# ProPrj_NavBot-ChargeModule-2S_2026-01-14.net
KiCad netlist of a schematic drawn in EasyEDA Pro
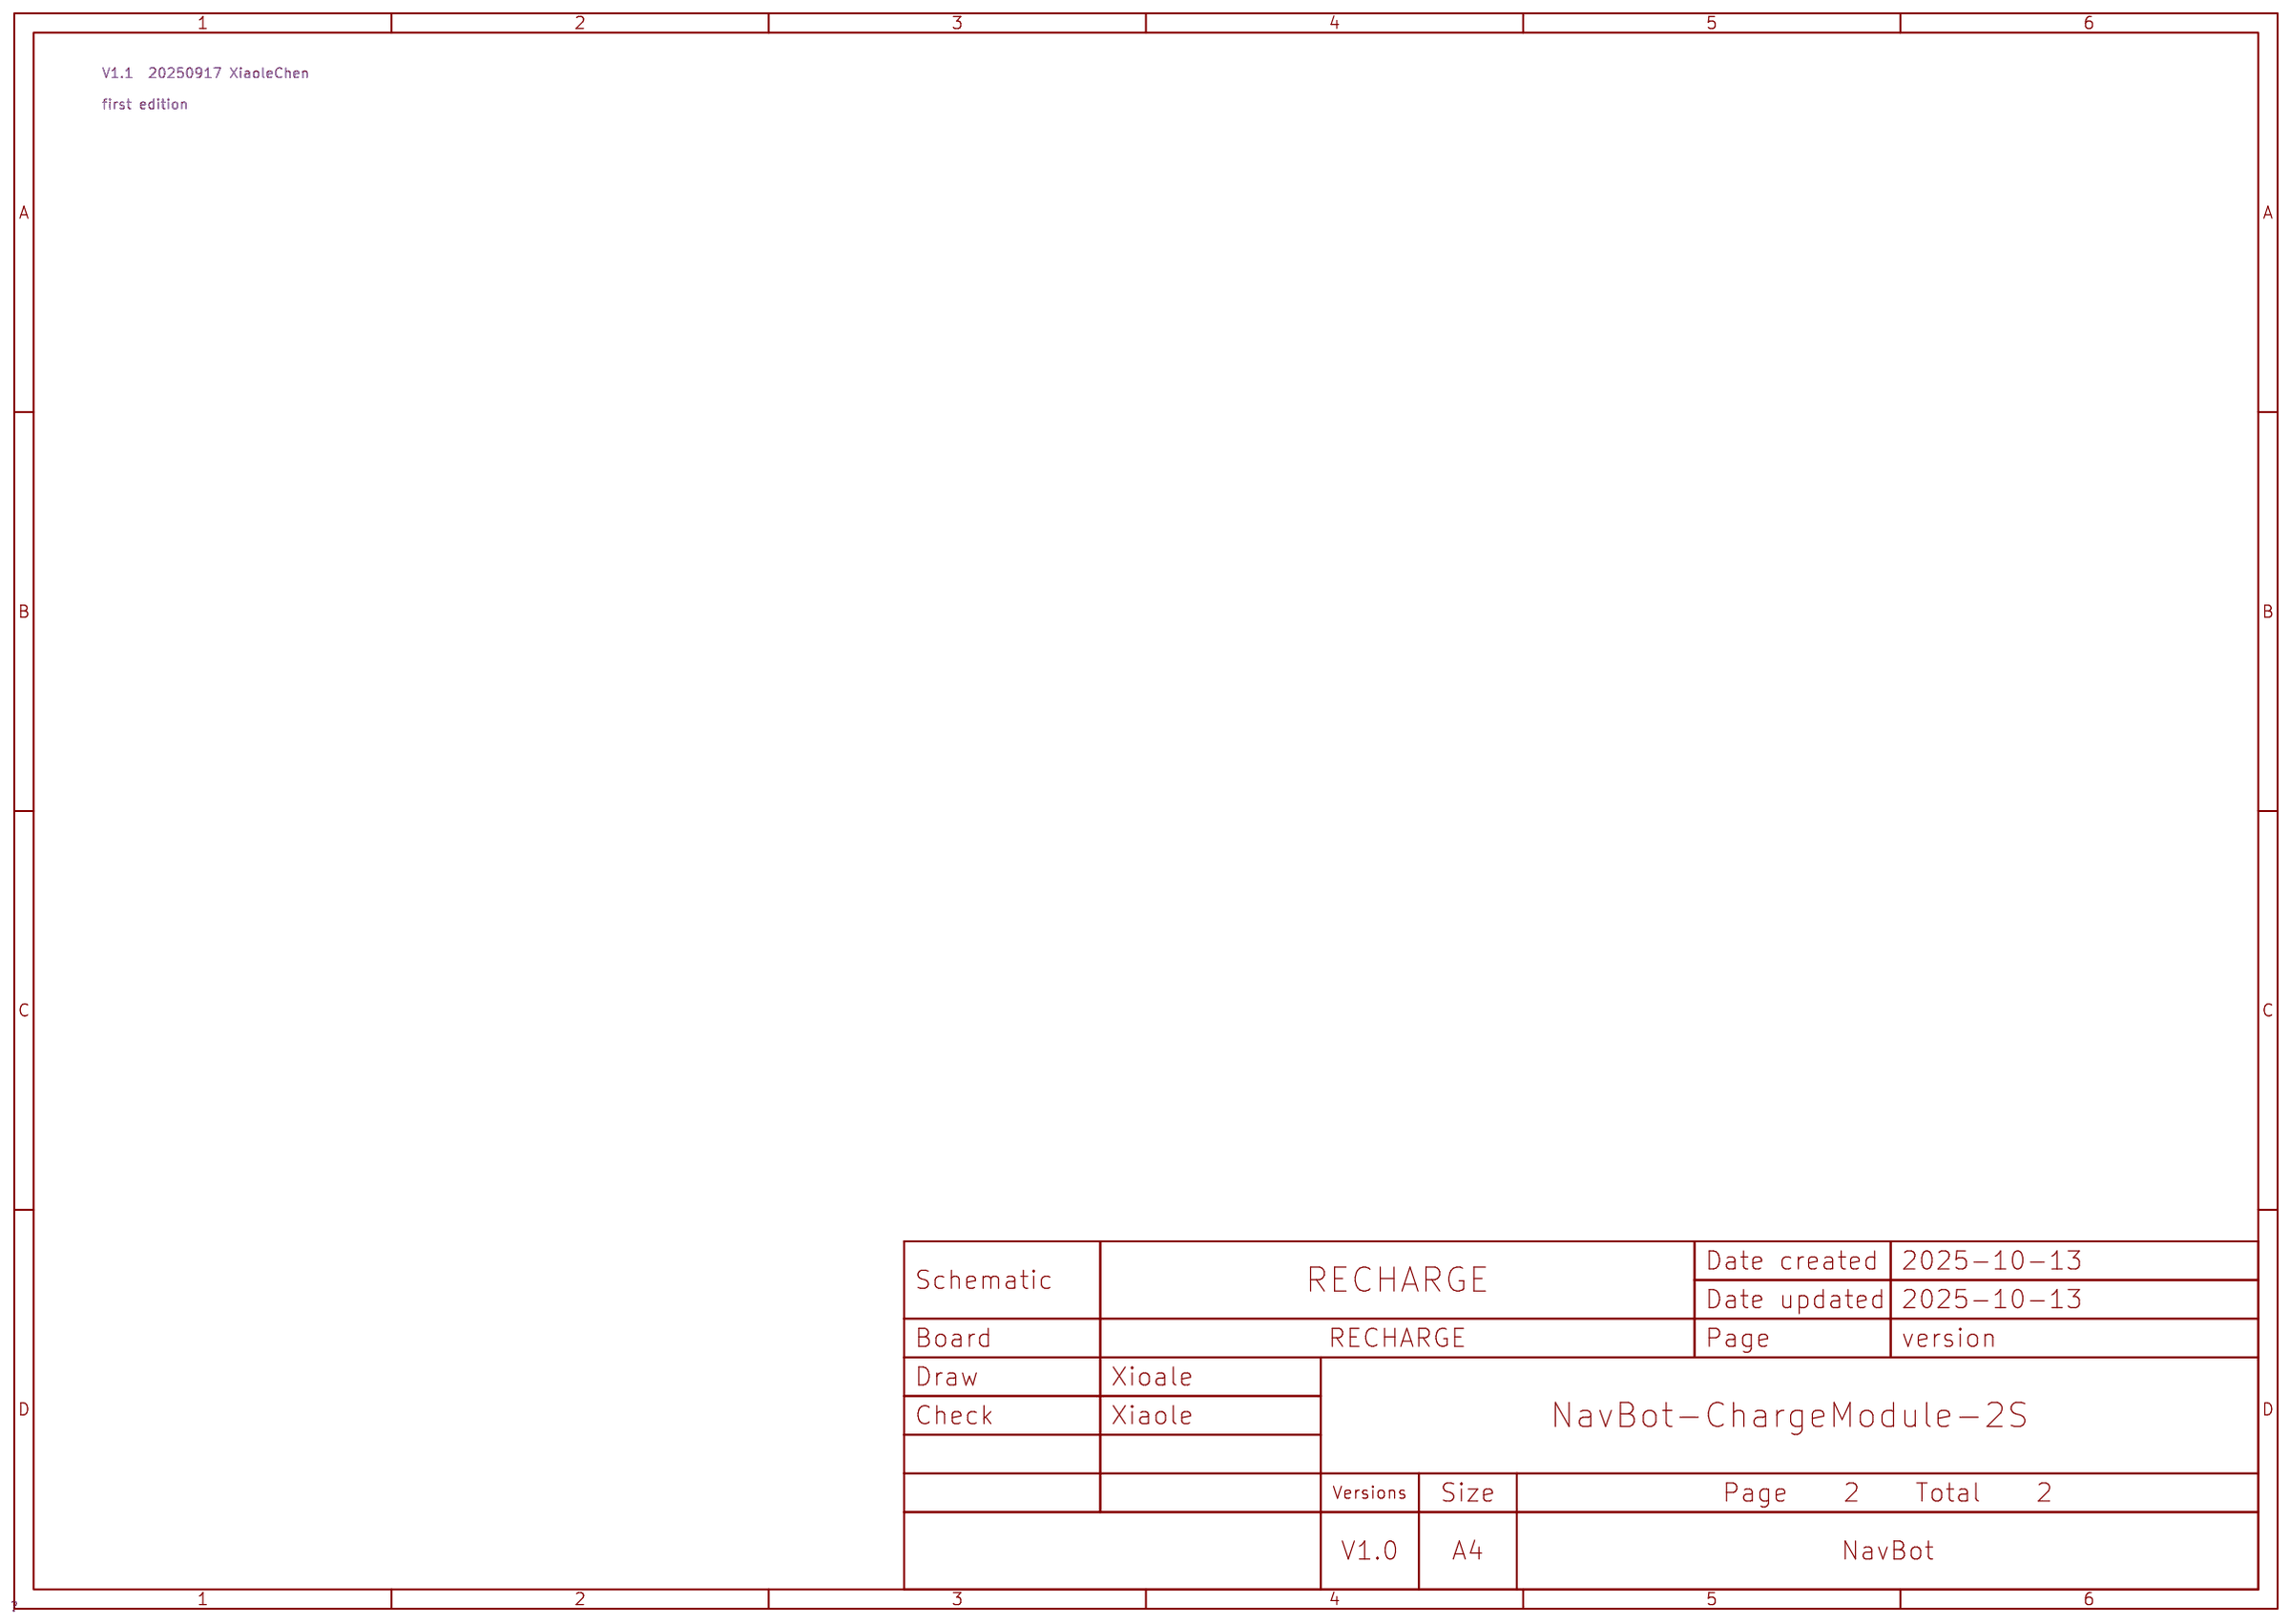
[diagram p0: version]
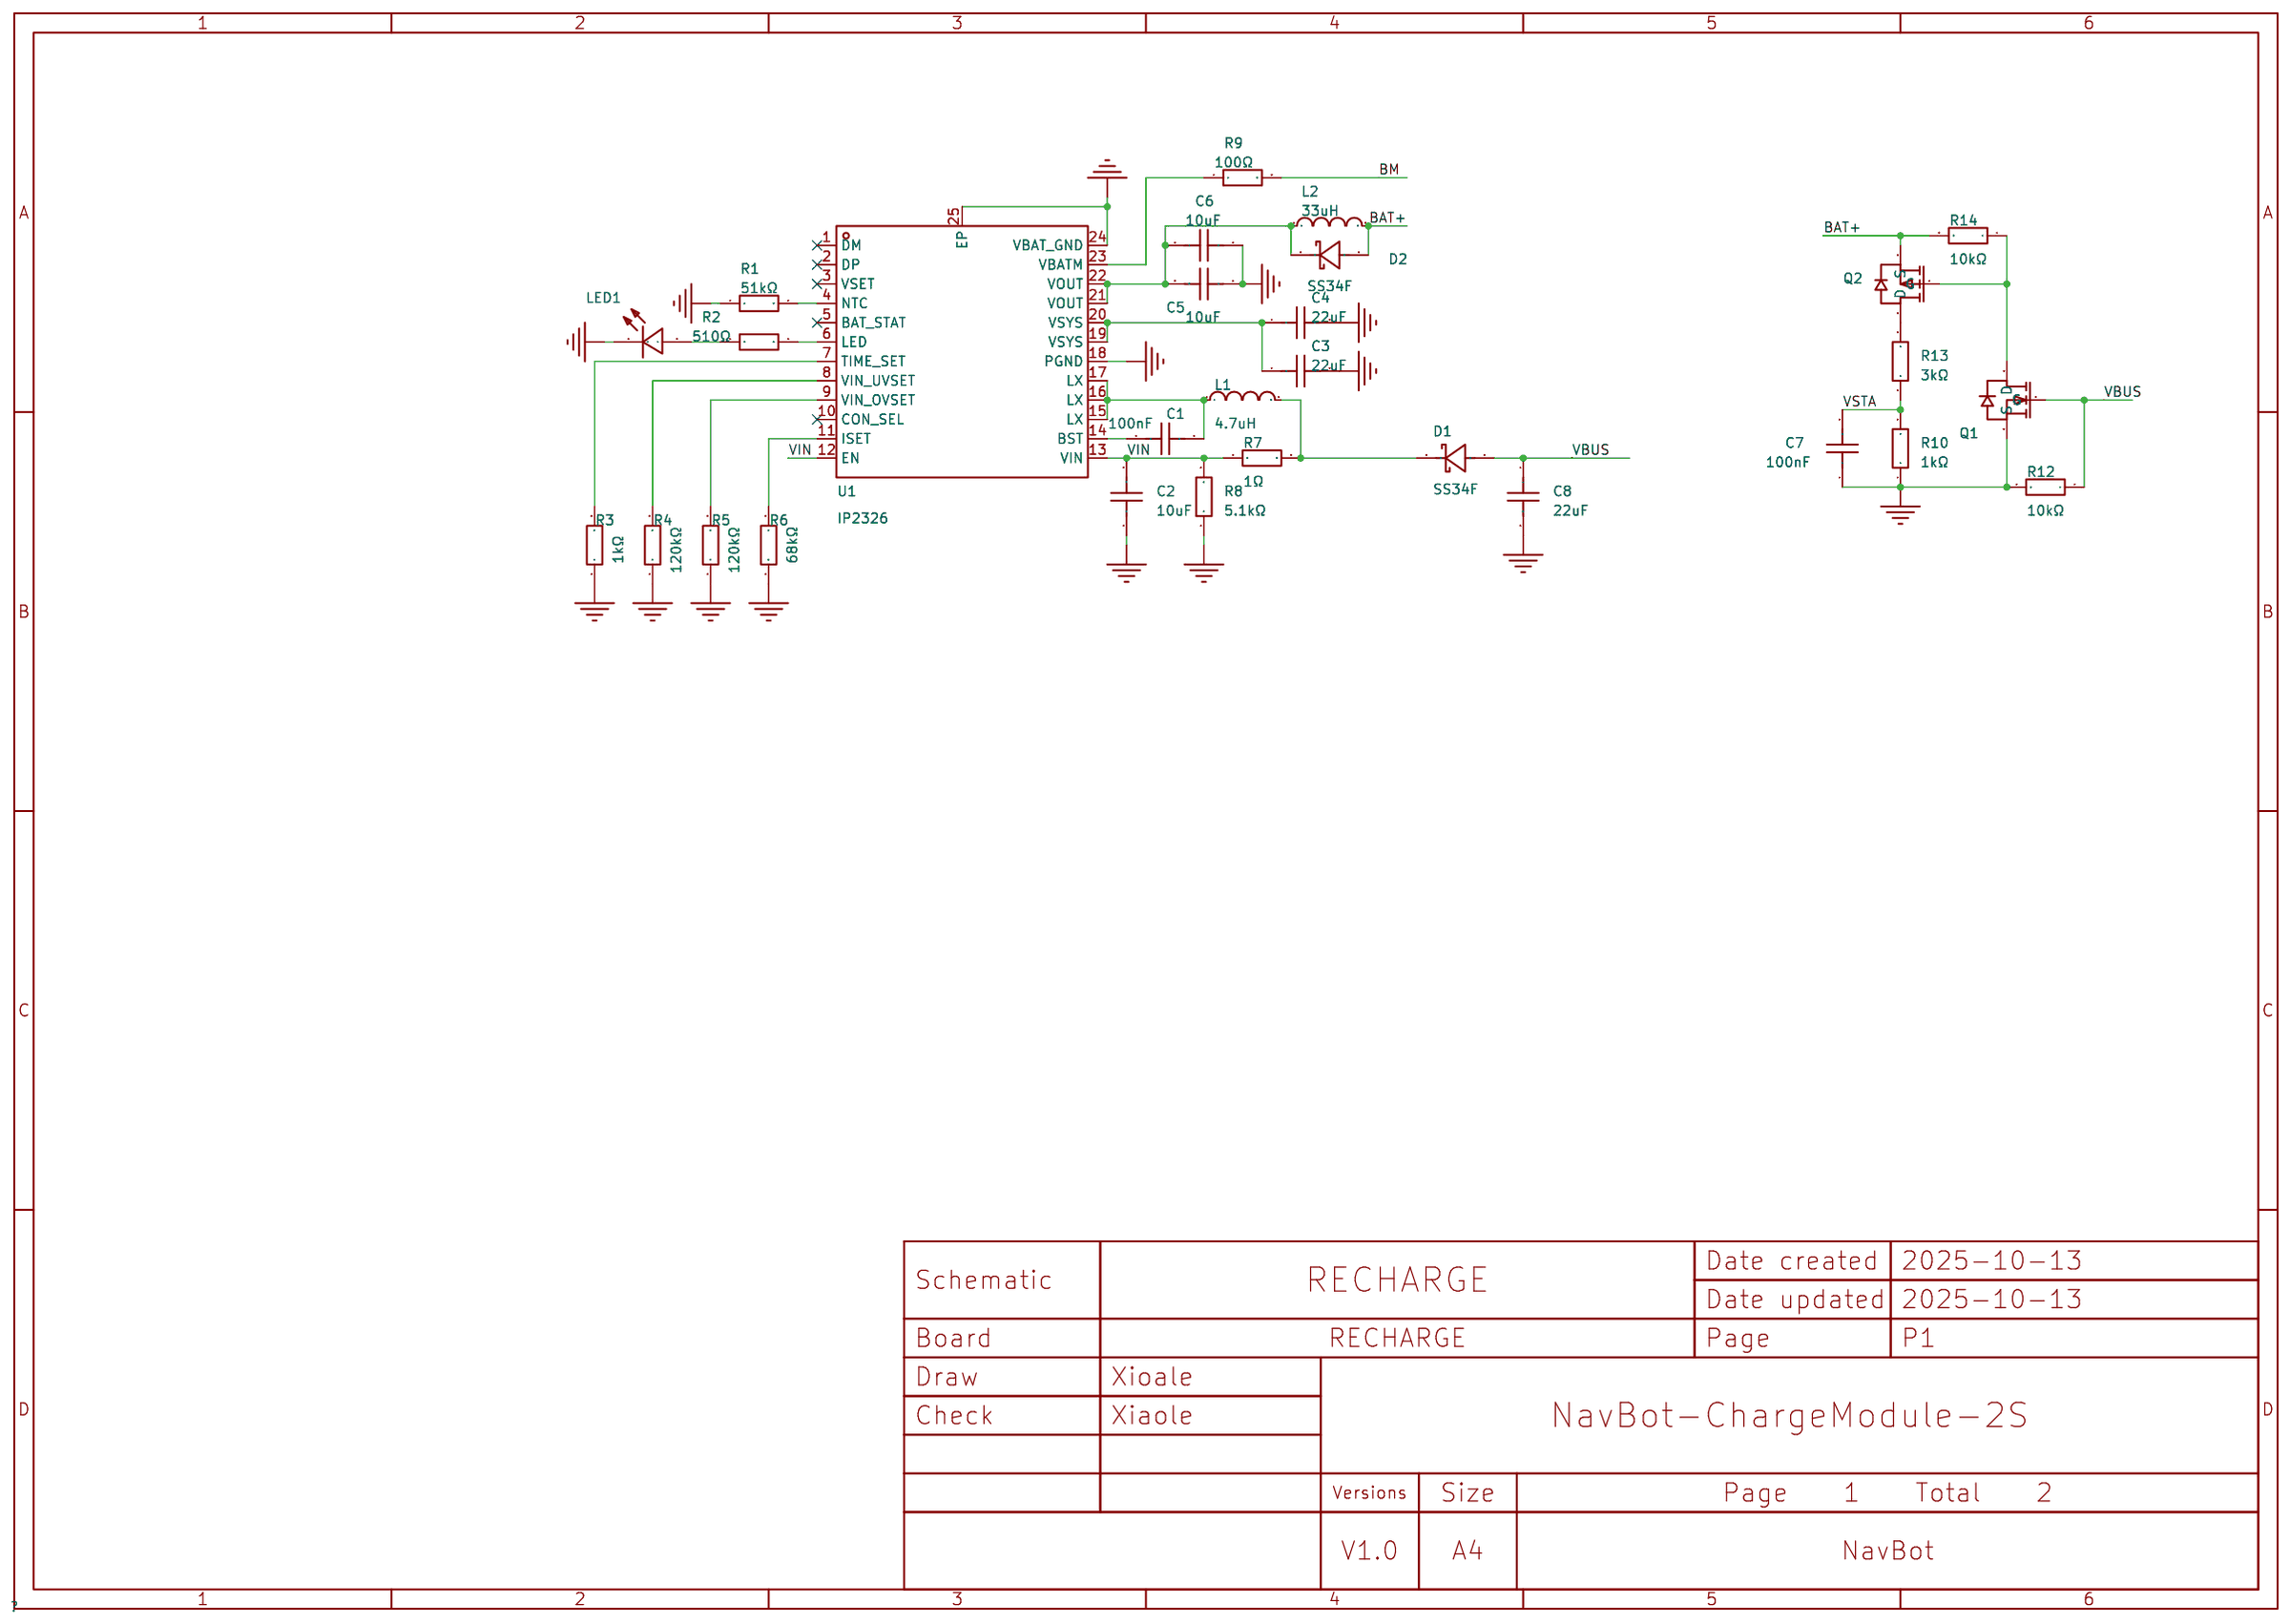
[diagram p1: P1]

(export (version "E")
  (design (tool "Eeschema 10.0.6"))
  (components
    (comp (ref "C1")
      (value "100nF")
      (footprint "easyedapro:C0603")
      (fields
        (field (name "Manufacturer Part") "CC0603KRX7R9BB104")
        (field (name "Manufacturer") "YAGEO(国巨)")
      )
      (libsource (lib "easyedapro") (part "CC0603KRX7R9BB104"))
    )
    (comp (ref "C2")
      (value "10uF")
      (footprint "easyedapro:C0603")
      (fields
        (field (name "Manufacturer Part") "CL10A106MA8NRNC")
        (field (name "Manufacturer") "SAMSUNG(三星)")
      )
      (libsource (lib "easyedapro") (part "CL10A106MA8NRNC"))
    )
    (comp (ref "C3")
      (value "22uF")
      (footprint "easyedapro:C0805")
      (fields
        (field (name "Manufacturer Part") "CL21A226MAQNNNE")
        (field (name "Manufacturer") "SAMSUNG(三星)")
      )
      (libsource (lib "easyedapro") (part "CL21A226MAQNNNE"))
    )
    (comp (ref "C4")
      (value "22uF")
      (footprint "easyedapro:C0805")
      (fields
        (field (name "Manufacturer Part") "CL21A226MAQNNNE")
        (field (name "Manufacturer") "SAMSUNG(三星)")
      )
      (libsource (lib "easyedapro") (part "CL21A226MAQNNNE"))
    )
    (comp (ref "C5")
      (value "10uF")
      (footprint "easyedapro:C0603")
      (fields
        (field (name "Manufacturer Part") "CL10A106MA8NRNC")
        (field (name "Manufacturer") "SAMSUNG(三星)")
      )
      (libsource (lib "easyedapro") (part "CL10A106MA8NRNC"))
    )
    (comp (ref "C6")
      (value "10uF")
      (footprint "easyedapro:C0603")
      (fields
        (field (name "Manufacturer Part") "CL10A106MA8NRNC")
        (field (name "Manufacturer") "SAMSUNG(三星)")
      )
      (libsource (lib "easyedapro") (part "CL10A106MA8NRNC"))
    )
    (comp (ref "C7")
      (value "100nF")
      (footprint "easyedapro:C0603")
      (fields
        (field (name "Manufacturer Part") "CC0603KRX7R9BB104")
        (field (name "Manufacturer") "YAGEO(国巨)")
      )
      (libsource (lib "easyedapro") (part "CC0603KRX7R9BB104"))
    )
    (comp (ref "C8")
      (value "22uF")
      (footprint "easyedapro:C0805")
      (fields
        (field (name "Manufacturer Part") "CL21A226MAQNNNE")
        (field (name "Manufacturer") "SAMSUNG(三星)")
      )
      (libsource (lib "easyedapro") (part "CL21A226MAQNNNE"))
    )
    (comp (ref "D1")
      (value "SS34F")
      (footprint "easyedapro:SMAF_L3.5-W2.6-LS4.7-RD-1")
      (fields (field (name "Manufacturer") "R+O(宏嘉诚)"))
      (libsource (lib "easyedapro") (part "SS34F_C18199199"))
    )
    (comp (ref "D2")
      (value "SS34F")
      (footprint "easyedapro:SMAF_L3.5-W2.6-LS4.7-RD-1")
      (fields (field (name "Manufacturer") "R+O(宏嘉诚)"))
      (libsource (lib "easyedapro") (part "SS34F_C18199199"))
    )
    (comp (ref "L1")
      (value "4.7uH")
      (footprint "easyedapro:IND-SMD_L4.0-W4.0")
      (fields
        (field (name "Manufacturer Part") "FHD4012S-4R7MT")
        (field (name "Manufacturer") "cjiang(长江微电)")
      )
      (libsource (lib "easyedapro") (part "FHD4012S-4R7MT"))
    )
    (comp (ref "L2")
      (value "33uH")
      (footprint "easyedapro:IND-SMD_L4.0-W4.0")
      (fields
        (field (name "Manufacturer Part") "FHD4020S-330MT")
        (field (name "Manufacturer") "cjiang(长江微电)")
      )
      (libsource (lib "easyedapro") (part "FHD4020S-330MT"))
    )
    (comp (ref "LED1")
      (value "KT-0603R")
      (footprint "easyedapro:LED0603-RD")
      (fields (field (name "Manufacturer") "KENTO"))
      (libsource (lib "easyedapro") (part "KT-0603R"))
    )
    (comp (ref "Q1")
      (value "~")
      (footprint "easyedapro:SOT-23-3_L2.9-W1.3-P1.90-LS2.4-BR")
      (libsource (lib "easyedapro") (part "N_MOS"))
    )
    (comp (ref "Q2")
      (value "~")
      (footprint "easyedapro:AO3401A_SOT-23-3")
      (libsource (lib "easyedapro") (part "P_MOS"))
    )
    (comp (ref "R1")
      (value "51kΩ")
      (footprint "easyedapro:R0603")
      (fields
        (field (name "Manufacturer Part") "0603WAF5102T5E")
        (field (name "Manufacturer") "UNI-ROYAL(厚声)")
      )
      (libsource (lib "easyedapro") (part "0603WAF5102T5E"))
    )
    (comp (ref "R2")
      (value "510Ω")
      (footprint "easyedapro:R0603")
      (fields
        (field (name "Manufacturer Part") "0603WAF5100T5E")
        (field (name "Manufacturer") "UNI-ROYAL(厚声)")
      )
      (libsource (lib "easyedapro") (part "0603WAF5100T5E"))
    )
    (comp (ref "R3")
      (value "1kΩ")
      (footprint "easyedapro:R0603")
      (fields
        (field (name "Manufacturer Part") "0603WAF1001T5E")
        (field (name "Manufacturer") "UNI-ROYAL(厚声)")
      )
      (libsource (lib "easyedapro") (part "0603WAF1001T5E"))
    )
    (comp (ref "R4")
      (value "120kΩ")
      (footprint "easyedapro:R0603")
      (fields
        (field (name "Manufacturer Part") "0603WAF1203T5E")
        (field (name "Manufacturer") "UNI-ROYAL(厚声)")
      )
      (libsource (lib "easyedapro") (part "0603WAF1203T5E"))
    )
    (comp (ref "R5")
      (value "120kΩ")
      (footprint "easyedapro:R0603")
      (fields
        (field (name "Manufacturer Part") "0603WAF1203T5E")
        (field (name "Manufacturer") "UNI-ROYAL(厚声)")
      )
      (libsource (lib "easyedapro") (part "0603WAF1203T5E"))
    )
    (comp (ref "R6")
      (value "68kΩ")
      (footprint "easyedapro:R0603")
      (fields
        (field (name "Manufacturer Part") "0603WAF6802T5E")
        (field (name "Manufacturer") "UNI-ROYAL(厚声)")
      )
      (libsource (lib "easyedapro") (part "0603WAF6802T5E"))
    )
    (comp (ref "R7")
      (value "1Ω")
      (footprint "easyedapro:R0603")
      (fields
        (field (name "Manufacturer Part") "0603WAF100KT5E")
        (field (name "Manufacturer") "UNI-ROYAL(厚声)")
      )
      (libsource (lib "easyedapro") (part "0603WAF100KT5E"))
    )
    (comp (ref "R8")
      (value "5.1kΩ")
      (footprint "easyedapro:R0603")
      (fields
        (field (name "Manufacturer Part") "0603WAF5101T5E")
        (field (name "Manufacturer") "UNI-ROYAL(厚声)")
      )
      (libsource (lib "easyedapro") (part "0603WAF5101T5E"))
    )
    (comp (ref "R9")
      (value "100Ω")
      (footprint "easyedapro:R1206")
      (fields
        (field (name "Manufacturer Part") "1206W4F1000T5E")
        (field (name "Manufacturer") "UNI-ROYAL(厚声)")
      )
      (libsource (lib "easyedapro") (part "1206W4F1000T5E"))
    )
    (comp (ref "R10")
      (value "1kΩ")
      (footprint "easyedapro:R0603")
      (fields
        (field (name "Manufacturer Part") "0603WAF1001T5E")
        (field (name "Manufacturer") "UNI-ROYAL(厚声)")
      )
      (libsource (lib "easyedapro") (part "0603WAF1001T5E"))
    )
    (comp (ref "R12")
      (value "10kΩ")
      (footprint "easyedapro:R0603")
      (fields
        (field (name "Manufacturer Part") "0603WAF1002T5E")
        (field (name "Manufacturer") "UNI-ROYAL(厚声)")
      )
      (libsource (lib "easyedapro") (part "0603WAF1002T5E"))
    )
    (comp (ref "R13")
      (value "3kΩ")
      (footprint "easyedapro:R0603")
      (fields
        (field (name "Manufacturer Part") "0603WAF3001T5E")
        (field (name "Manufacturer") "UNI-ROYAL(厚声)")
      )
      (libsource (lib "easyedapro") (part "0603WAF3001T5E"))
    )
    (comp (ref "R14")
      (value "10kΩ")
      (footprint "easyedapro:R0603")
      (fields
        (field (name "Manufacturer Part") "0603WAF1002T5E")
        (field (name "Manufacturer") "UNI-ROYAL(厚声)")
      )
      (libsource (lib "easyedapro") (part "0603WAF1002T5E"))
    )
    (comp (ref "U1")
      (value "IP2326")
      (footprint "easyedapro:VQFN-24_L4.0-W4.0-P0.50-BL-EP2.5")
      (fields (field (name "Manufacturer") "INJOINIC(英集芯)"))
      (libsource (lib "easyedapro") (part "IP2326"))
    )
  )
  (nets
    (net (code "1") (name "BAT+") (class "Default")
      (node (ref "D2") (pin "2") (pinfunction "A_2") (pintype "unspecified"))
      (node (ref "L2") (pin "2") (pinfunction "2_2") (pintype "unspecified"))
      (node (ref "Q2") (pin "2") (pinfunction "S_2") (pintype "input"))
      (node (ref "R14") (pin "2") (pinfunction "2_2") (pintype "input"))
    )
    (net (code "2") (name "BM") (class "Default")
      (node (ref "R9") (pin "2") (pinfunction "2_2") (pintype "input"))
    )
    (net (code "3") (name "GND") (class "Default")
      (node (ref "C2") (pin "1") (pinfunction "1_1") (pintype "unspecified"))
      (node (ref "C3") (pin "2") (pinfunction "2_2") (pintype "unspecified"))
      (node (ref "C4") (pin "2") (pinfunction "2_2") (pintype "unspecified"))
      (node (ref "C5") (pin "1") (pinfunction "1_1") (pintype "unspecified"))
      (node (ref "C6") (pin "1") (pinfunction "1_1") (pintype "unspecified"))
      (node (ref "C7") (pin "1") (pinfunction "1_1") (pintype "unspecified"))
      (node (ref "C8") (pin "2") (pinfunction "2_2") (pintype "unspecified"))
      (node (ref "LED1") (pin "1") (pinfunction "K_1") (pintype "unspecified"))
      (node (ref "Q1") (pin "2") (pinfunction "S_2") (pintype "input"))
      (node (ref "R1") (pin "1") (pinfunction "1_1") (pintype "input"))
      (node (ref "R10") (pin "1") (pinfunction "1_1") (pintype "input"))
      (node (ref "R12") (pin "2") (pinfunction "2_2") (pintype "input"))
      (node (ref "R3") (pin "1") (pinfunction "1_1") (pintype "input"))
      (node (ref "R4") (pin "1") (pinfunction "1_1") (pintype "input"))
      (node (ref "R5") (pin "1") (pinfunction "1_1") (pintype "input"))
      (node (ref "R6") (pin "1") (pinfunction "1_1") (pintype "input"))
      (node (ref "R8") (pin "1") (pinfunction "1_1") (pintype "input"))
      (node (ref "U1") (pin "18") (pinfunction "PGND_18") (pintype "unspecified"))
      (node (ref "U1") (pin "24") (pinfunction "VBAT_GND_24") (pintype "unspecified"))
      (node (ref "U1") (pin "25") (pinfunction "EP_25") (pintype "unspecified"))
    )
    (net (code "4") (name "Net-(C1-Pad2)") (class "Default")
      (node (ref "C1") (pin "2") (pinfunction "2_2") (pintype "unspecified"))
      (node (ref "L1") (pin "1") (pinfunction "1_1") (pintype "unspecified"))
      (node (ref "U1") (pin "15") (pinfunction "LX_15") (pintype "unspecified"))
      (node (ref "U1") (pin "16") (pinfunction "LX_16") (pintype "unspecified"))
      (node (ref "U1") (pin "17") (pinfunction "LX_17") (pintype "unspecified"))
    )
    (net (code "5") (name "Net-(C3-Pad1)") (class "Default")
      (node (ref "C3") (pin "1") (pinfunction "1_1") (pintype "unspecified"))
      (node (ref "C4") (pin "1") (pinfunction "1_1") (pintype "unspecified"))
      (node (ref "U1") (pin "19") (pinfunction "VSYS_19") (pintype "unspecified"))
      (node (ref "U1") (pin "20") (pinfunction "VSYS_20") (pintype "unspecified"))
    )
    (net (code "6") (name "Net-(D1-K)") (class "Default")
      (node (ref "D1") (pin "1") (pinfunction "K_1") (pintype "unspecified"))
      (node (ref "L1") (pin "2") (pinfunction "2_2") (pintype "unspecified"))
      (node (ref "R7") (pin "2") (pinfunction "2_2") (pintype "input"))
    )
    (net (code "7") (name "Net-(D2-K)") (class "Default")
      (node (ref "C5") (pin "2") (pinfunction "2_2") (pintype "unspecified"))
      (node (ref "C6") (pin "2") (pinfunction "2_2") (pintype "unspecified"))
      (node (ref "D2") (pin "1") (pinfunction "K_1") (pintype "unspecified"))
      (node (ref "L2") (pin "1") (pinfunction "1_1") (pintype "unspecified"))
      (node (ref "U1") (pin "21") (pinfunction "VOUT_21") (pintype "unspecified"))
      (node (ref "U1") (pin "22") (pinfunction "VOUT_22") (pintype "unspecified"))
    )
    (net (code "8") (name "Net-(LED1-A)") (class "Default")
      (node (ref "LED1") (pin "2") (pinfunction "A_2") (pintype "unspecified"))
      (node (ref "R2") (pin "1") (pinfunction "1_1") (pintype "input"))
    )
    (net (code "9") (name "Net-(Q1-D)") (class "Default")
      (node (ref "Q1") (pin "3") (pinfunction "D_3") (pintype "input"))
      (node (ref "Q2") (pin "1") (pinfunction "G_1") (pintype "input"))
      (node (ref "R14") (pin "1") (pinfunction "1_1") (pintype "input"))
    )
    (net (code "10") (name "Net-(Q2-D)") (class "Default")
      (node (ref "Q2") (pin "3") (pinfunction "D_3") (pintype "input"))
      (node (ref "R13") (pin "2") (pinfunction "2_2") (pintype "input"))
    )
    (net (code "11") (name "Net-(U1-BST)") (class "Default")
      (node (ref "C1") (pin "1") (pinfunction "1_1") (pintype "unspecified"))
      (node (ref "U1") (pin "14") (pinfunction "BST_14") (pintype "unspecified"))
    )
    (net (code "12") (name "Net-(U1-ISET)") (class "Default")
      (node (ref "R6") (pin "2") (pinfunction "2_2") (pintype "input"))
      (node (ref "U1") (pin "11") (pinfunction "ISET_11") (pintype "unspecified"))
    )
    (net (code "13") (name "Net-(U1-LED)") (class "Default")
      (node (ref "R2") (pin "2") (pinfunction "2_2") (pintype "input"))
      (node (ref "U1") (pin "6") (pinfunction "LED_6") (pintype "unspecified"))
    )
    (net (code "14") (name "Net-(U1-NTC)") (class "Default")
      (node (ref "R1") (pin "2") (pinfunction "2_2") (pintype "input"))
      (node (ref "U1") (pin "4") (pinfunction "NTC_4") (pintype "unspecified"))
    )
    (net (code "15") (name "Net-(U1-TIME_SET)") (class "Default")
      (node (ref "R3") (pin "2") (pinfunction "2_2") (pintype "input"))
      (node (ref "U1") (pin "7") (pinfunction "TIME_SET_7") (pintype "unspecified"))
    )
    (net (code "16") (name "Net-(U1-VBATM)") (class "Default")
      (node (ref "R9") (pin "1") (pinfunction "1_1") (pintype "input"))
      (node (ref "U1") (pin "23") (pinfunction "VBATM_23") (pintype "unspecified"))
    )
    (net (code "17") (name "Net-(U1-VIN_OVSET)") (class "Default")
      (node (ref "R5") (pin "2") (pinfunction "2_2") (pintype "input"))
      (node (ref "U1") (pin "9") (pinfunction "VIN_OVSET_9") (pintype "unspecified"))
    )
    (net (code "18") (name "Net-(U1-VIN_UVSET)") (class "Default")
      (node (ref "R4") (pin "2") (pinfunction "2_2") (pintype "input"))
      (node (ref "U1") (pin "8") (pinfunction "VIN_UVSET_8") (pintype "unspecified"))
    )
    (net (code "19") (name "VBUS") (class "Default")
      (node (ref "C8") (pin "1") (pinfunction "1_1") (pintype "unspecified"))
      (node (ref "D1") (pin "2") (pinfunction "A_2") (pintype "unspecified"))
      (node (ref "Q1") (pin "1") (pinfunction "G_1") (pintype "input"))
      (node (ref "R12") (pin "1") (pinfunction "1_1") (pintype "input"))
    )
    (net (code "20") (name "VIN") (class "Default")
      (node (ref "C2") (pin "2") (pinfunction "2_2") (pintype "unspecified"))
      (node (ref "R7") (pin "1") (pinfunction "1_1") (pintype "input"))
      (node (ref "R8") (pin "2") (pinfunction "2_2") (pintype "input"))
      (node (ref "U1") (pin "12") (pinfunction "EN_12") (pintype "unspecified"))
      (node (ref "U1") (pin "13") (pinfunction "VIN_13") (pintype "unspecified"))
    )
    (net (code "21") (name "VSTA") (class "Default")
      (node (ref "C7") (pin "2") (pinfunction "2_2") (pintype "unspecified"))
      (node (ref "R10") (pin "2") (pinfunction "2_2") (pintype "input"))
      (node (ref "R13") (pin "1") (pinfunction "1_1") (pintype "input"))
    )
    (net (code "22") (name "unconnected-(U1-BAT_STAT-Pad5)") (class "Default")
      (node (ref "U1") (pin "5") (pinfunction "BAT_STAT_5") (pintype "unspecified+no_connect"))
    )
    (net (code "23") (name "unconnected-(U1-CON_SEL-Pad10)") (class "Default")
      (node (ref "U1") (pin "10") (pinfunction "CON_SEL_10") (pintype "unspecified+no_connect"))
    )
    (net (code "24") (name "unconnected-(U1-DM-Pad1)") (class "Default")
      (node (ref "U1") (pin "1") (pinfunction "DM_1") (pintype "unspecified+no_connect"))
    )
    (net (code "25") (name "unconnected-(U1-DP-Pad2)") (class "Default")
      (node (ref "U1") (pin "2") (pinfunction "DP_2") (pintype "unspecified+no_connect"))
    )
    (net (code "26") (name "unconnected-(U1-VSET-Pad3)") (class "Default")
      (node (ref "U1") (pin "3") (pinfunction "VSET_3") (pintype "unspecified+no_connect"))
    )
  )
)
